# Esquema.net
KiCad netlist of a schematic drawn in EAGLE
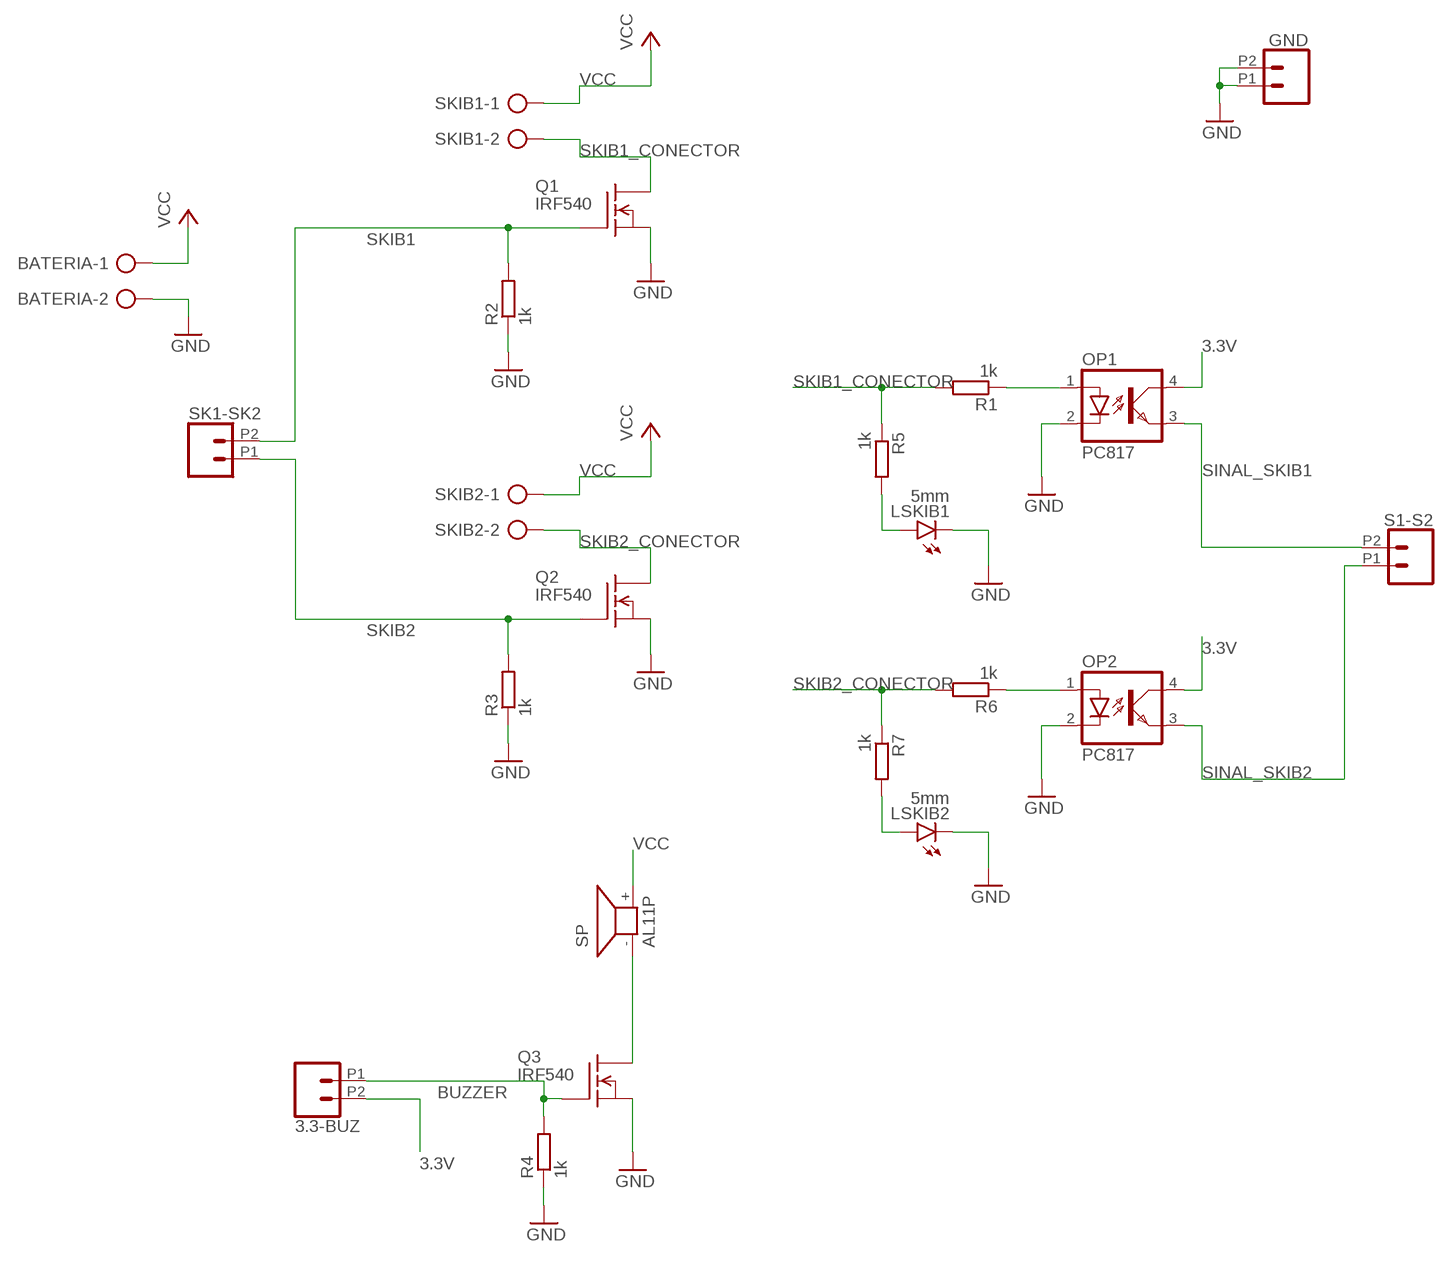
[diagram p0: schematic, sheet 1]

(export (version "E")
  (design (tool "Eeschema 10.0.6"))
  (components
    (comp (ref "3.3-BUZ")
      (value "CONN_022.54MM_SCREWTERM")
      (footprint "eagle-import:1X02_2.54_SCREWTERM")
      (libsource (lib "eagle-import") (part "CONN_022.54MM_SCREWTERM"))
    )
    (comp (ref "BATERIA")
      (value "AK500/2-H")
      (footprint "eagle-import:AK500_2-H")
      (libsource (lib "eagle-import") (part "AK500/2-H"))
    )
    (comp (ref "GND")
      (value "CONN_022.54MM_SCREWTERM")
      (footprint "eagle-import:1X02_2.54_SCREWTERM")
      (libsource (lib "eagle-import") (part "CONN_022.54MM_SCREWTERM"))
    )
    (comp (ref "LSKIB1")
      (value "5mm")
      (footprint "eagle-import:LED5MM")
      (libsource (lib "eagle-import") (part "LED5MM"))
    )
    (comp (ref "LSKIB2")
      (value "5mm")
      (footprint "eagle-import:LED5MM")
      (libsource (lib "eagle-import") (part "LED5MM"))
    )
    (comp (ref "OP1")
      (value "PC817")
      (footprint "eagle-import:DIL04")
      (fields (field (name "MPN") "PC817X4J000F"))
      (libsource (lib "eagle-import") (part "PC817"))
    )
    (comp (ref "OP2")
      (value "PC817")
      (footprint "eagle-import:DIL04")
      (fields (field (name "MPN") "PC817X4J000F"))
      (libsource (lib "eagle-import") (part "PC817"))
    )
    (comp (ref "Q1")
      (value "IRF540")
      (footprint "eagle-import:TO220")
      (libsource (lib "eagle-import") (part "IRF540"))
    )
    (comp (ref "Q2")
      (value "IRF540")
      (footprint "eagle-import:TO220")
      (libsource (lib "eagle-import") (part "IRF540"))
    )
    (comp (ref "Q3")
      (value "IRF540")
      (footprint "eagle-import:TO220")
      (libsource (lib "eagle-import") (part "IRF540"))
    )
    (comp (ref "R1")
      (value "1k")
      (footprint "eagle-import:0207_10")
      (libsource (lib "eagle-import") (part "R-EU_0207/10"))
    )
    (comp (ref "R2")
      (value "1k")
      (footprint "eagle-import:0207_10")
      (libsource (lib "eagle-import") (part "R-EU_0207/10"))
    )
    (comp (ref "R3")
      (value "1k")
      (footprint "eagle-import:0207_10")
      (libsource (lib "eagle-import") (part "R-EU_0207/10"))
    )
    (comp (ref "R4")
      (value "1k")
      (footprint "eagle-import:0207_10")
      (libsource (lib "eagle-import") (part "R-EU_0207/10"))
    )
    (comp (ref "R5")
      (value "1k")
      (footprint "eagle-import:0207_10")
      (libsource (lib "eagle-import") (part "R-EU_0207/10"))
    )
    (comp (ref "R6")
      (value "1k")
      (footprint "eagle-import:0207_10")
      (libsource (lib "eagle-import") (part "R-EU_0207/10"))
    )
    (comp (ref "R7")
      (value "1k")
      (footprint "eagle-import:0207_10")
      (libsource (lib "eagle-import") (part "R-EU_0207/10"))
    )
    (comp (ref "S1-S2")
      (value "CONN_022.54MM_SCREWTERM")
      (footprint "eagle-import:1X02_2.54_SCREWTERM")
      (libsource (lib "eagle-import") (part "CONN_022.54MM_SCREWTERM"))
    )
    (comp (ref "SK1-SK2")
      (value "CONN_022.54MM_SCREWTERM")
      (footprint "eagle-import:1X02_2.54_SCREWTERM")
      (libsource (lib "eagle-import") (part "CONN_022.54MM_SCREWTERM"))
    )
    (comp (ref "SKIB1")
      (value "AK500/2-H")
      (footprint "eagle-import:AK500_2-H")
      (libsource (lib "eagle-import") (part "AK500/2-H"))
    )
    (comp (ref "SKIB2")
      (value "AK500/2-H")
      (footprint "eagle-import:AK500_2-H")
      (libsource (lib "eagle-import") (part "AK500/2-H"))
    )
    (comp (ref "SP")
      (value "AL11P")
      (footprint "eagle-import:AL11P")
      (libsource (lib "eagle-import") (part "AL11P"))
    )
  )
  (nets
    (net (code "1") (name "/3.3V") (class "Default")
      (node (ref "3.3-BUZ") (pin "P2") (pinfunction "2_P2") (pintype "passive"))
      (node (ref "OP1") (pin "4") (pinfunction "COL_4") (pintype "passive"))
      (node (ref "OP2") (pin "4") (pinfunction "COL_4") (pintype "passive"))
    )
    (net (code "2") (name "/BUZZER") (class "Default")
      (node (ref "3.3-BUZ") (pin "P1") (pinfunction "1_P1") (pintype "passive"))
      (node (ref "Q3") (pin "1") (pinfunction "G_1") (pintype "passive"))
      (node (ref "R4") (pin "2") (pinfunction "2_2") (pintype "passive"))
    )
    (net (code "3") (name "/SINAL_SKIB1") (class "Default")
      (node (ref "OP1") (pin "3") (pinfunction "EMIT_3") (pintype "passive"))
      (node (ref "S1-S2") (pin "P2") (pinfunction "2_P2") (pintype "passive"))
    )
    (net (code "4") (name "/SINAL_SKIB2") (class "Default")
      (node (ref "OP2") (pin "3") (pinfunction "EMIT_3") (pintype "passive"))
      (node (ref "S1-S2") (pin "P1") (pinfunction "1_P1") (pintype "passive"))
    )
    (net (code "5") (name "/SKIB1") (class "Default")
      (node (ref "Q1") (pin "1") (pinfunction "G_1") (pintype "passive"))
      (node (ref "R2") (pin "2") (pinfunction "2_2") (pintype "passive"))
      (node (ref "SK1-SK2") (pin "P2") (pinfunction "2_P2") (pintype "passive"))
    )
    (net (code "6") (name "/SKIB1_CONECTOR") (class "Default")
      (node (ref "Q1") (pin "2") (pinfunction "D_2") (pintype "passive"))
      (node (ref "R1") (pin "2") (pinfunction "2_2") (pintype "passive"))
      (node (ref "R5") (pin "1") (pinfunction "1_1") (pintype "passive"))
      (node (ref "SKIB1") (pin "2") (pinfunction "KL_2") (pintype "passive"))
    )
    (net (code "7") (name "/SKIB2") (class "Default")
      (node (ref "Q2") (pin "1") (pinfunction "G_1") (pintype "passive"))
      (node (ref "R3") (pin "2") (pinfunction "2_2") (pintype "passive"))
      (node (ref "SK1-SK2") (pin "P1") (pinfunction "1_P1") (pintype "passive"))
    )
    (net (code "8") (name "/SKIB2_CONECTOR") (class "Default")
      (node (ref "Q2") (pin "2") (pinfunction "D_2") (pintype "passive"))
      (node (ref "R6") (pin "2") (pinfunction "2_2") (pintype "passive"))
      (node (ref "R7") (pin "1") (pinfunction "1_1") (pintype "passive"))
      (node (ref "SKIB2") (pin "2") (pinfunction "KL_2") (pintype "passive"))
    )
    (net (code "9") (name "GND") (class "Default")
      (node (ref "BATERIA") (pin "2") (pinfunction "KL_2") (pintype "passive"))
      (node (ref "GND") (pin "P1") (pinfunction "1_P1") (pintype "passive"))
      (node (ref "GND") (pin "P2") (pinfunction "2_P2") (pintype "passive"))
      (node (ref "LSKIB1") (pin "K") (pinfunction "C_K") (pintype "passive"))
      (node (ref "LSKIB2") (pin "K") (pinfunction "C_K") (pintype "passive"))
      (node (ref "OP1") (pin "2") (pinfunction "C_2") (pintype "passive"))
      (node (ref "OP2") (pin "2") (pinfunction "C_2") (pintype "passive"))
      (node (ref "Q1") (pin "3") (pinfunction "S_3") (pintype "passive"))
      (node (ref "Q2") (pin "3") (pinfunction "S_3") (pintype "passive"))
      (node (ref "Q3") (pin "3") (pinfunction "S_3") (pintype "passive"))
      (node (ref "R2") (pin "1") (pinfunction "1_1") (pintype "passive"))
      (node (ref "R3") (pin "1") (pinfunction "1_1") (pintype "passive"))
      (node (ref "R4") (pin "1") (pinfunction "1_1") (pintype "passive"))
    )
    (net (code "10") (name "Net-(LSKIB1-PadA)") (class "Default")
      (node (ref "LSKIB1") (pin "A") (pinfunction "A_A") (pintype "passive"))
      (node (ref "R5") (pin "2") (pinfunction "2_2") (pintype "passive"))
    )
    (net (code "11") (name "Net-(LSKIB2-PadA)") (class "Default")
      (node (ref "LSKIB2") (pin "A") (pinfunction "A_A") (pintype "passive"))
      (node (ref "R7") (pin "2") (pinfunction "2_2") (pintype "passive"))
    )
    (net (code "12") (name "Net-(OP1-A)") (class "Default")
      (node (ref "OP1") (pin "1") (pinfunction "A_1") (pintype "passive"))
      (node (ref "R1") (pin "1") (pinfunction "1_1") (pintype "passive"))
    )
    (net (code "13") (name "Net-(OP2-A)") (class "Default")
      (node (ref "OP2") (pin "1") (pinfunction "A_1") (pintype "passive"))
      (node (ref "R6") (pin "1") (pinfunction "1_1") (pintype "passive"))
    )
    (net (code "14") (name "Net-(Q3-D)") (class "Default")
      (node (ref "Q3") (pin "2") (pinfunction "D_2") (pintype "passive"))
      (node (ref "SP") (pin "-") (pinfunction "1_-") (pintype "passive"))
    )
    (net (code "15") (name "VCC") (class "Default")
      (node (ref "BATERIA") (pin "1") (pinfunction "KL_1") (pintype "passive"))
      (node (ref "SKIB1") (pin "1") (pinfunction "KL_1") (pintype "passive"))
      (node (ref "SKIB2") (pin "1") (pinfunction "KL_1") (pintype "passive"))
      (node (ref "SP") (pin "+") (pinfunction "2_+") (pintype "passive"))
    )
  )
)
